# usb_board.net
KiCad netlist of a schematic drawn in EAGLE
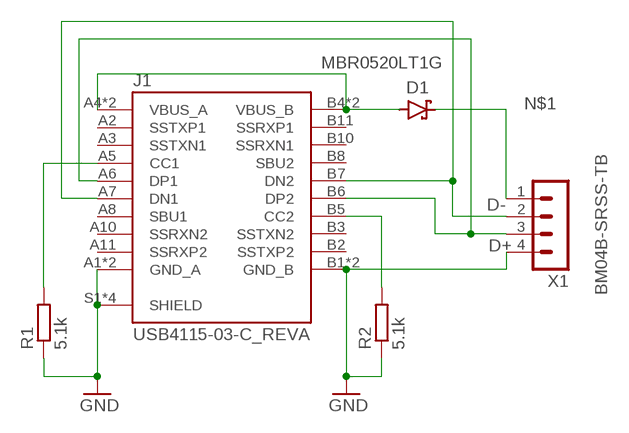
[diagram p0: schematic, sheet 1]

(export (version "E")
  (design (tool "Eeschema 10.0.6"))
  (components
    (comp (ref "D1")
      (value "MBR0520LT1G")
      (footprint "eagle-import:SODFL3718X115")
      (fields (field (name "MANUFACTURER") "ON Semiconductor"))
      (libsource (lib "eagle-import") (part "SCHOTTKY_DO-219MBR0520LT1G"))
    )
    (comp (ref "J1")
      (value "USB4115-03-C_REVA")
      (footprint "eagle-import:GCT_USB4115-03-C_REVA")
      (fields (field (name "MF") "Global Connector Technology") (field (name "MP") "USB4115-03-C"))
      (libsource (lib "eagle-import") (part "USB4115-03-C_REVA"))
    )
    (comp (ref "R1")
      (value "5.1k")
      (footprint "eagle-import:R0805")
      (libsource (lib "eagle-import") (part "R-EU_R0805"))
    )
    (comp (ref "R2")
      (value "5.1k")
      (footprint "eagle-import:R0805")
      (libsource (lib "eagle-import") (part "R-EU_R0805"))
    )
    (comp (ref "X1")
      (value "BM04B-SRSS-TB")
      (footprint "eagle-import:BM04B-SRSS-TB")
      (libsource (lib "eagle-import") (part "BM04B-SRSS-TB"))
    )
  )
  (nets
    (net (code "1") (name "/D+") (class "Default")
      (node (ref "J1") (pin "A6") (pinfunction "DP1_A6") (pintype "bidirectional"))
      (node (ref "J1") (pin "B6") (pinfunction "DP2_B6") (pintype "bidirectional"))
      (node (ref "X1") (pin "3") (pinfunction "3_3") (pintype "passive"))
    )
    (net (code "2") (name "/D-") (class "Default")
      (node (ref "J1") (pin "A7") (pinfunction "DN1_A7") (pintype "bidirectional"))
      (node (ref "J1") (pin "B7") (pinfunction "DN2_B7") (pintype "bidirectional"))
      (node (ref "X1") (pin "2") (pinfunction "2_2") (pintype "passive"))
    )
    (net (code "3") (name "/N$1") (class "Default")
      (node (ref "D1") (pin "1") (pinfunction "C_1") (pintype "passive"))
      (node (ref "X1") (pin "1") (pinfunction "1_1") (pintype "passive"))
    )
    (net (code "4") (name "GND") (class "Default")
      (node (ref "J1") (pin "A1") (pinfunction "GND_A_A1") (pintype "power_in"))
      (node (ref "J1") (pin "A12") (pinfunction "GND_A_A12") (pintype "power_in"))
      (node (ref "J1") (pin "B1") (pinfunction "GND_B_B1") (pintype "power_in"))
      (node (ref "J1") (pin "B12") (pinfunction "GND_B_B12") (pintype "power_in"))
      (node (ref "J1") (pin "S1") (pinfunction "SHIELD_S1") (pintype "passive"))
      (node (ref "J1") (pin "S2") (pinfunction "SHIELD_S2") (pintype "passive"))
      (node (ref "J1") (pin "S3") (pinfunction "SHIELD_S3") (pintype "passive"))
      (node (ref "J1") (pin "S4") (pinfunction "SHIELD_S4") (pintype "passive"))
      (node (ref "R1") (pin "1") (pinfunction "1_1") (pintype "passive"))
      (node (ref "R2") (pin "1") (pinfunction "1_1") (pintype "passive"))
      (node (ref "X1") (pin "4") (pinfunction "4_4") (pintype "passive"))
    )
    (net (code "5") (name "Net-(D1-A)") (class "Default")
      (node (ref "D1") (pin "2") (pinfunction "A_2") (pintype "passive"))
      (node (ref "J1") (pin "A4") (pinfunction "VBUS_A_A4") (pintype "power_in"))
      (node (ref "J1") (pin "A9") (pinfunction "VBUS_A_A9") (pintype "power_in"))
      (node (ref "J1") (pin "B4") (pinfunction "VBUS_B_B4") (pintype "power_in"))
      (node (ref "J1") (pin "B9") (pinfunction "VBUS_B_B9") (pintype "power_in"))
    )
    (net (code "6") (name "Net-(J1-CC1)") (class "Default")
      (node (ref "J1") (pin "A5") (pinfunction "CC1_A5") (pintype "bidirectional"))
      (node (ref "R1") (pin "2") (pinfunction "2_2") (pintype "passive"))
    )
    (net (code "7") (name "Net-(J1-CC2)") (class "Default")
      (node (ref "J1") (pin "B5") (pinfunction "CC2_B5") (pintype "bidirectional"))
      (node (ref "R2") (pin "2") (pinfunction "2_2") (pintype "passive"))
    )
    (net (code "8") (name "unconnected-(J1-SBU1-PadA8)") (class "Default")
      (node (ref "J1") (pin "A8") (pinfunction "SBU1_A8") (pintype "bidirectional"))
    )
    (net (code "9") (name "unconnected-(J1-SBU2-PadB8)") (class "Default")
      (node (ref "J1") (pin "B8") (pinfunction "SBU2_B8") (pintype "bidirectional"))
    )
    (net (code "10") (name "unconnected-(J1-SSRXN1-PadB10)") (class "Default")
      (node (ref "J1") (pin "B10") (pinfunction "SSRXN1_B10") (pintype "bidirectional"))
    )
    (net (code "11") (name "unconnected-(J1-SSRXN2-PadA10)") (class "Default")
      (node (ref "J1") (pin "A10") (pinfunction "SSRXN2_A10") (pintype "bidirectional"))
    )
    (net (code "12") (name "unconnected-(J1-SSRXP1-PadB11)") (class "Default")
      (node (ref "J1") (pin "B11") (pinfunction "SSRXP1_B11") (pintype "bidirectional"))
    )
    (net (code "13") (name "unconnected-(J1-SSRXP2-PadA11)") (class "Default")
      (node (ref "J1") (pin "A11") (pinfunction "SSRXP2_A11") (pintype "bidirectional"))
    )
    (net (code "14") (name "unconnected-(J1-SSTXN1-PadA3)") (class "Default")
      (node (ref "J1") (pin "A3") (pinfunction "SSTXN1_A3") (pintype "bidirectional"))
    )
    (net (code "15") (name "unconnected-(J1-SSTXN2-PadB3)") (class "Default")
      (node (ref "J1") (pin "B3") (pinfunction "SSTXN2_B3") (pintype "bidirectional"))
    )
    (net (code "16") (name "unconnected-(J1-SSTXP1-PadA2)") (class "Default")
      (node (ref "J1") (pin "A2") (pinfunction "SSTXP1_A2") (pintype "bidirectional"))
    )
    (net (code "17") (name "unconnected-(J1-SSTXP2-PadB2)") (class "Default")
      (node (ref "J1") (pin "B2") (pinfunction "SSTXP2_B2") (pintype "bidirectional"))
    )
  )
)
